# SparkFun_NEO-M8U.net
KiCad netlist of a schematic drawn in EAGLE
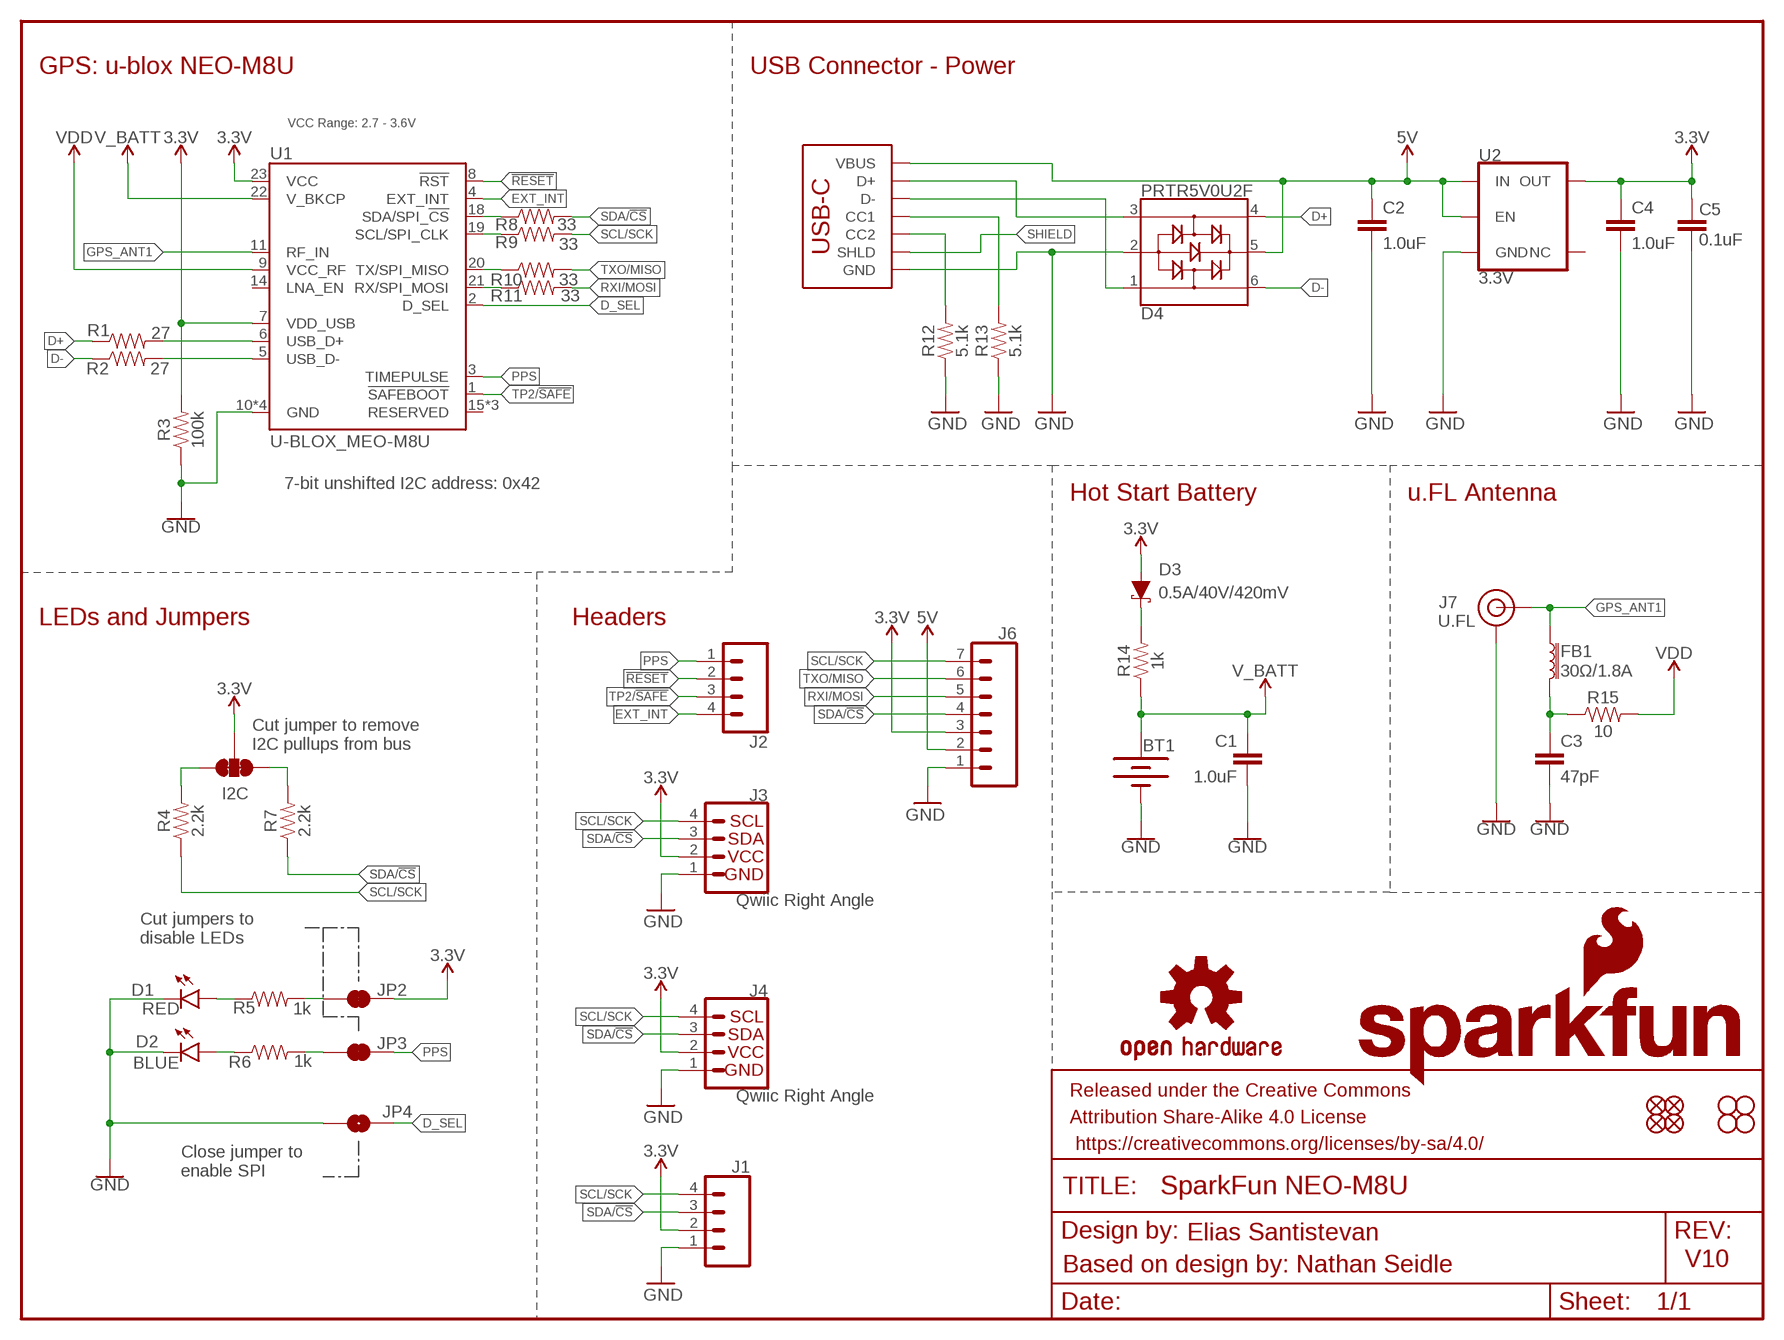
[diagram p0: schematic, sheet 1]

(export (version "E")
  (design (tool "Eeschema 10.0.6"))
  (components
    (comp (ref "BT1")
      (value "6.8MM_COIN_CELL")
      (footprint "eagle-import:ML414H_IV01E")
      (libsource (lib "eagle-import") (part "ML414H_IV01E_BATTERY"))
    )
    (comp (ref "C1")
      (value "1.0uF")
      (footprint "eagle-import:0603")
      (libsource (lib "eagle-import") (part "1.0UF-0603-16V-10%"))
    )
    (comp (ref "C2")
      (value "1.0uF")
      (footprint "eagle-import:0603")
      (libsource (lib "eagle-import") (part "1.0UF-0603-16V-10%"))
    )
    (comp (ref "C3")
      (value "47pF")
      (footprint "eagle-import:0603")
      (libsource (lib "eagle-import") (part "47PF-0603-50V-5%"))
    )
    (comp (ref "C4")
      (value "1.0uF")
      (footprint "eagle-import:0603")
      (libsource (lib "eagle-import") (part "1.0UF-0603-16V-10%"))
    )
    (comp (ref "C5")
      (value "0.1uF")
      (footprint "eagle-import:0603")
      (libsource (lib "eagle-import") (part "0.1UF-0603-25V-(+80/-20%)"))
    )
    (comp (ref "D1")
      (value "RED")
      (footprint "eagle-import:LED-0603")
      (libsource (lib "eagle-import") (part "LED-RED0603"))
    )
    (comp (ref "D2")
      (value "BLUE")
      (footprint "eagle-import:LED-0603")
      (libsource (lib "eagle-import") (part "LED-BLUE0603"))
    )
    (comp (ref "D3")
      (value "0.5A/40V/420mV")
      (footprint "eagle-import:SOD-323")
      (libsource (lib "eagle-import") (part "DIODE-SCHOTTKY-PMEG4005EJ"))
    )
    (comp (ref "D4")
      (value "PRTR5V0U2F")
      (footprint "eagle-import:SOT886")
      (libsource (lib "eagle-import") (part "PRTR5V0U2F"))
    )
    (comp (ref "FB1")
      (value "30Ω/1.8A")
      (footprint "eagle-import:0603")
      (libsource (lib "eagle-import") (part "FERRITE_BEAD-0603"))
    )
    (comp (ref "FRAME1")
      (value "FRAME-LETTER")
      (footprint "eagle-import:CREATIVE_COMMONS")
      (libsource (lib "eagle-import") (part "FRAME-LETTER"))
    )
    (comp (ref "J1")
      (value "CONN_041X04_NO_SILK")
      (footprint "eagle-import:1X04_NO_SILK")
      (libsource (lib "eagle-import") (part "CONN_041X04_NO_SILK"))
    )
    (comp (ref "J2")
      (value "CONN_041X04_NO_SILK")
      (footprint "eagle-import:1X04_NO_SILK")
      (libsource (lib "eagle-import") (part "CONN_041X04_NO_SILK"))
    )
    (comp (ref "J3")
      (value "Qwiic Right Angle")
      (footprint "eagle-import:JST04_1MM_RA")
      (libsource (lib "eagle-import") (part "I2C_STANDARDQWIIC"))
    )
    (comp (ref "J4")
      (value "Qwiic Right Angle")
      (footprint "eagle-import:JST04_1MM_RA")
      (libsource (lib "eagle-import") (part "I2C_STANDARDQWIIC"))
    )
    (comp (ref "J5")
      (value "USB_C_2-LAYER_PADS")
      (footprint "eagle-import:USB-C-16P-2LAYER-PADS")
      (libsource (lib "eagle-import") (part "USB_C_2-LAYER_PADS"))
    )
    (comp (ref "J6")
      (value "CONN_07NO_SILK")
      (footprint "eagle-import:1X07_NO_SILK")
      (libsource (lib "eagle-import") (part "CONN_07NO_SILK"))
    )
    (comp (ref "J7")
      (value "U.FL")
      (footprint "eagle-import:U.FL")
      (libsource (lib "eagle-import") (part "U.FL2PIN"))
    )
    (comp (ref "JP1")
      (value "JUMPER-SMT_3_2-NC_TRACE_SILK")
      (footprint "eagle-import:SMT-JUMPER_3_2-NC_TRACE_SILK")
      (libsource (lib "eagle-import") (part "JUMPER-SMT_3_2-NC_TRACE_SILK"))
    )
    (comp (ref "JP2")
      (value "JUMPER-SMT_2_NC_TRACE_SILK")
      (footprint "eagle-import:SMT-JUMPER_2_NC_TRACE_SILK")
      (libsource (lib "eagle-import") (part "JUMPER-SMT_2_NC_TRACE_SILK"))
    )
    (comp (ref "JP3")
      (value "JUMPER-SMT_2_NC_TRACE_SILK")
      (footprint "eagle-import:SMT-JUMPER_2_NC_TRACE_SILK")
      (libsource (lib "eagle-import") (part "JUMPER-SMT_2_NC_TRACE_SILK"))
    )
    (comp (ref "JP4")
      (value "JUMPER-SMT_2_NO_SILK")
      (footprint "eagle-import:SMT-JUMPER_2_NO_SILK")
      (libsource (lib "eagle-import") (part "JUMPER-SMT_2_NO_SILK"))
    )
    (comp (ref "JP5")
      (value "FIDUCIALUFIDUCIAL")
      (footprint "eagle-import:MICRO-FIDUCIAL")
      (libsource (lib "eagle-import") (part "FIDUCIALUFIDUCIAL"))
    )
    (comp (ref "JP6")
      (value "FIDUCIALUFIDUCIAL")
      (footprint "eagle-import:MICRO-FIDUCIAL")
      (libsource (lib "eagle-import") (part "FIDUCIALUFIDUCIAL"))
    )
    (comp (ref "JP7")
      (value "FIDUCIALUFIDUCIAL")
      (footprint "eagle-import:MICRO-FIDUCIAL")
      (libsource (lib "eagle-import") (part "FIDUCIALUFIDUCIAL"))
    )
    (comp (ref "JP8")
      (value "FIDUCIALUFIDUCIAL")
      (footprint "eagle-import:MICRO-FIDUCIAL")
      (libsource (lib "eagle-import") (part "FIDUCIALUFIDUCIAL"))
    )
    (comp (ref "JP9")
      (value "STAND-OFF")
      (footprint "eagle-import:STAND-OFF")
      (libsource (lib "eagle-import") (part "STAND-OFF"))
    )
    (comp (ref "JP10")
      (value "STAND-OFF")
      (footprint "eagle-import:STAND-OFF")
      (libsource (lib "eagle-import") (part "STAND-OFF"))
    )
    (comp (ref "JP11")
      (value "STAND-OFF")
      (footprint "eagle-import:STAND-OFF")
      (libsource (lib "eagle-import") (part "STAND-OFF"))
    )
    (comp (ref "JP12")
      (value "STAND-OFF")
      (footprint "eagle-import:STAND-OFF")
      (libsource (lib "eagle-import") (part "STAND-OFF"))
    )
    (comp (ref "LOGO1")
      (value "OSHW-LOGOMINI")
      (footprint "eagle-import:OSHW-LOGO-MINI")
      (libsource (lib "eagle-import") (part "OSHW-LOGOMINI"))
    )
    (comp (ref "LOGO2")
      (value "SFE_LOGO_NAME_FLAME.1_INCH")
      (footprint "eagle-import:SFE_LOGO_NAME_FLAME_.1")
      (libsource (lib "eagle-import") (part "SFE_LOGO_NAME_FLAME.1_INCH"))
    )
    (comp (ref "R1")
      (value "27")
      (footprint "eagle-import:0603")
      (libsource (lib "eagle-import") (part "27OHM-0603-1/10W-1%"))
    )
    (comp (ref "R2")
      (value "27")
      (footprint "eagle-import:0603")
      (libsource (lib "eagle-import") (part "27OHM-0603-1/10W-1%"))
    )
    (comp (ref "R3")
      (value "100k")
      (footprint "eagle-import:0603")
      (libsource (lib "eagle-import") (part "100KOHM-0603-1/10W-1%"))
    )
    (comp (ref "R4")
      (value "2.2k")
      (footprint "eagle-import:0603")
      (libsource (lib "eagle-import") (part "2.2KOHM-0603-1/10W-1%"))
    )
    (comp (ref "R5")
      (value "1k")
      (footprint "eagle-import:0603")
      (libsource (lib "eagle-import") (part "1KOHM-0603-1/10W-1%"))
    )
    (comp (ref "R6")
      (value "1k")
      (footprint "eagle-import:0603")
      (libsource (lib "eagle-import") (part "1KOHM-0603-1/10W-1%"))
    )
    (comp (ref "R7")
      (value "2.2k")
      (footprint "eagle-import:0603")
      (libsource (lib "eagle-import") (part "2.2KOHM-0603-1/10W-1%"))
    )
    (comp (ref "R8")
      (value "33")
      (footprint "eagle-import:0603")
      (libsource (lib "eagle-import") (part "33OHM-0603-1/10W-1%"))
    )
    (comp (ref "R9")
      (value "33")
      (footprint "eagle-import:0603")
      (libsource (lib "eagle-import") (part "33OHM-0603-1/10W-1%"))
    )
    (comp (ref "R10")
      (value "33")
      (footprint "eagle-import:0603")
      (libsource (lib "eagle-import") (part "33OHM-0603-1/10W-1%"))
    )
    (comp (ref "R11")
      (value "33")
      (footprint "eagle-import:0603")
      (libsource (lib "eagle-import") (part "33OHM-0603-1/10W-1%"))
    )
    (comp (ref "R12")
      (value "5.1k")
      (footprint "eagle-import:0603")
      (libsource (lib "eagle-import") (part "5.1KOHM5.1KOHM-0603-1/10W-1%"))
    )
    (comp (ref "R13")
      (value "5.1k")
      (footprint "eagle-import:0603")
      (libsource (lib "eagle-import") (part "5.1KOHM5.1KOHM-0603-1/10W-1%"))
    )
    (comp (ref "R14")
      (value "1k")
      (footprint "eagle-import:0603")
      (libsource (lib "eagle-import") (part "1KOHM-0603-1/10W-1%"))
    )
    (comp (ref "R15")
      (value "10")
      (footprint "eagle-import:0603")
      (libsource (lib "eagle-import") (part "10OHM-0603-1/10W-1%"))
    )
    (comp (ref "U1")
      (value "U-BLOX_MEO-M8U")
      (footprint "eagle-import:NEO-M9N_M8T_M8U")
      (libsource (lib "eagle-import") (part "U-BLOX_MEO-M8U"))
    )
    (comp (ref "U2")
      (value "3.3V")
      (footprint "eagle-import:SOT23-5")
      (libsource (lib "eagle-import") (part "V_REG_AP2112K-3.3V"))
    )
  )
  (nets
    (net (code "1") (name "/SDA{slash}~{CS}") (class "Default")
      (node (ref "J1") (pin "3") (pinfunction "3_3") (pintype "passive"))
      (node (ref "J3") (pin "3") (pinfunction "3_3") (pintype "passive"))
      (node (ref "J4") (pin "3") (pinfunction "3_3") (pintype "passive"))
      (node (ref "J6") (pin "4") (pinfunction "4_4") (pintype "passive"))
      (node (ref "R7") (pin "1") (pinfunction "1_1") (pintype "passive"))
      (node (ref "R8") (pin "2") (pinfunction "2_2") (pintype "passive"))
    )
    (net (code "2") (name "/TP2{slash}~{SAFE}") (class "Default")
      (node (ref "J2") (pin "3") (pinfunction "3_3") (pintype "passive"))
      (node (ref "U1") (pin "1") (pinfunction "~{SAFEBOOT}_1") (pintype "bidirectional"))
    )
    (net (code "3") (name "/~{RESET}") (class "Default")
      (node (ref "J2") (pin "2") (pinfunction "2_2") (pintype "passive"))
      (node (ref "U1") (pin "8") (pinfunction "~{RST}_8") (pintype "bidirectional"))
    )
    (net (code "4") (name "3.3V") (class "Default")
      (node (ref "C4") (pin "1") (pinfunction "1_1") (pintype "passive"))
      (node (ref "C5") (pin "2") (pinfunction "2_2") (pintype "passive"))
      (node (ref "D3") (pin "A") (pinfunction "A_A") (pintype "passive"))
      (node (ref "J1") (pin "2") (pinfunction "2_2") (pintype "passive"))
      (node (ref "J3") (pin "2") (pinfunction "2_2") (pintype "power_in"))
      (node (ref "J4") (pin "2") (pinfunction "2_2") (pintype "power_in"))
      (node (ref "J6") (pin "3") (pinfunction "3_3") (pintype "passive"))
      (node (ref "JP1") (pin "2") (pinfunction "2_2") (pintype "passive"))
      (node (ref "JP2") (pin "2") (pinfunction "2_2") (pintype "passive"))
      (node (ref "R3") (pin "2") (pinfunction "2_2") (pintype "passive"))
      (node (ref "U1") (pin "23") (pinfunction "VCC_23") (pintype "bidirectional"))
      (node (ref "U1") (pin "7") (pinfunction "VDD_USB_7") (pintype "bidirectional"))
      (node (ref "U2") (pin "5") (pinfunction "OUT_5") (pintype "passive"))
    )
    (net (code "5") (name "5V") (class "Default")
      (node (ref "C2") (pin "1") (pinfunction "1_1") (pintype "passive"))
      (node (ref "D4") (pin "5") (pinfunction "5_5") (pintype "bidirectional"))
      (node (ref "J5") (pin "VBUS1") (pinfunction "VBUS_VBUS1") (pintype "bidirectional"))
      (node (ref "J5") (pin "VBUS2") (pinfunction "VBUS_VBUS2") (pintype "bidirectional"))
      (node (ref "J6") (pin "2") (pinfunction "2_2") (pintype "passive"))
      (node (ref "U2") (pin "1") (pinfunction "IN_1") (pintype "input"))
      (node (ref "U2") (pin "3") (pinfunction "EN_3") (pintype "input"))
    )
    (net (code "6") (name "D+") (class "Default")
      (node (ref "D4") (pin "4") (pinfunction "4_4") (pintype "bidirectional"))
      (node (ref "R1") (pin "1") (pinfunction "1_1") (pintype "passive"))
    )
    (net (code "7") (name "D-") (class "Default")
      (node (ref "D4") (pin "6") (pinfunction "6_6") (pintype "bidirectional"))
      (node (ref "R2") (pin "1") (pinfunction "1_1") (pintype "passive"))
    )
    (net (code "8") (name "D_SEL") (class "Default")
      (node (ref "JP4") (pin "2") (pinfunction "2_2") (pintype "passive"))
      (node (ref "U1") (pin "2") (pinfunction "D_SEL_2") (pintype "bidirectional"))
    )
    (net (code "9") (name "EXT_INT") (class "Default")
      (node (ref "J2") (pin "4") (pinfunction "4_4") (pintype "passive"))
      (node (ref "U1") (pin "4") (pinfunction "EXT_INT_4") (pintype "bidirectional"))
    )
    (net (code "10") (name "GND") (class "Default")
      (node (ref "BT1") (pin "-") (pinfunction "-_-") (pintype "power_in"))
      (node (ref "C1") (pin "2") (pinfunction "2_2") (pintype "passive"))
      (node (ref "C2") (pin "2") (pinfunction "2_2") (pintype "passive"))
      (node (ref "C3") (pin "2") (pinfunction "2_2") (pintype "passive"))
      (node (ref "C4") (pin "2") (pinfunction "2_2") (pintype "passive"))
      (node (ref "C5") (pin "1") (pinfunction "1_1") (pintype "passive"))
      (node (ref "D1") (pin "C") (pinfunction "C_C") (pintype "passive"))
      (node (ref "D2") (pin "C") (pinfunction "C_C") (pintype "passive"))
      (node (ref "D4") (pin "2") (pinfunction "2_2") (pintype "bidirectional"))
      (node (ref "J1") (pin "1") (pinfunction "1_1") (pintype "passive"))
      (node (ref "J3") (pin "1") (pinfunction "1_1") (pintype "power_in"))
      (node (ref "J4") (pin "1") (pinfunction "1_1") (pintype "power_in"))
      (node (ref "J5") (pin "GND") (pinfunction "GND_GND") (pintype "bidirectional"))
      (node (ref "J5") (pin "GND2") (pinfunction "GND_GND2") (pintype "bidirectional"))
      (node (ref "J6") (pin "1") (pinfunction "1_1") (pintype "passive"))
      (node (ref "J7") (pin "1") (pinfunction "GND_1") (pintype "bidirectional"))
      (node (ref "J7") (pin "2") (pinfunction "GND_2") (pintype "bidirectional"))
      (node (ref "JP4") (pin "1") (pinfunction "1_1") (pintype "passive"))
      (node (ref "R12") (pin "1") (pinfunction "1_1") (pintype "passive"))
      (node (ref "R13") (pin "1") (pinfunction "1_1") (pintype "passive"))
      (node (ref "R3") (pin "1") (pinfunction "1_1") (pintype "passive"))
      (node (ref "U1") (pin "10") (pinfunction "GND_10") (pintype "bidirectional"))
      (node (ref "U1") (pin "12") (pinfunction "GND_12") (pintype "bidirectional"))
      (node (ref "U1") (pin "13") (pinfunction "GND_13") (pintype "bidirectional"))
      (node (ref "U1") (pin "24") (pinfunction "GND_24") (pintype "bidirectional"))
      (node (ref "U2") (pin "2") (pinfunction "GND_2") (pintype "input"))
    )
    (net (code "11") (name "GPS_ANT1") (class "Default")
      (node (ref "FB1") (pin "1") (pinfunction "1_1") (pintype "passive"))
      (node (ref "J7") (pin "FEED") (pinfunction "SIGNAL_FEED") (pintype "bidirectional"))
      (node (ref "U1") (pin "11") (pinfunction "RF_IN_11") (pintype "bidirectional"))
    )
    (net (code "12") (name "Net-(C3-Pad1)") (class "Default")
      (node (ref "C3") (pin "1") (pinfunction "1_1") (pintype "passive"))
      (node (ref "FB1") (pin "2") (pinfunction "2_2") (pintype "passive"))
      (node (ref "R15") (pin "1") (pinfunction "1_1") (pintype "passive"))
    )
    (net (code "13") (name "Net-(D1-PadA)") (class "Default")
      (node (ref "D1") (pin "A") (pinfunction "A_A") (pintype "passive"))
      (node (ref "R5") (pin "1") (pinfunction "1_1") (pintype "passive"))
    )
    (net (code "14") (name "Net-(D2-PadA)") (class "Default")
      (node (ref "D2") (pin "A") (pinfunction "A_A") (pintype "passive"))
      (node (ref "R6") (pin "1") (pinfunction "1_1") (pintype "passive"))
    )
    (net (code "15") (name "Net-(D3-PadC)") (class "Default")
      (node (ref "D3") (pin "C") (pinfunction "C_C") (pintype "passive"))
      (node (ref "R14") (pin "2") (pinfunction "2_2") (pintype "passive"))
    )
    (net (code "16") (name "Net-(D4-Pad1)") (class "Default")
      (node (ref "D4") (pin "1") (pinfunction "1_1") (pintype "bidirectional"))
      (node (ref "J5") (pin "A7") (pinfunction "D-_A7") (pintype "bidirectional"))
      (node (ref "J5") (pin "B7") (pinfunction "D-_B7") (pintype "bidirectional"))
    )
    (net (code "17") (name "Net-(D4-Pad3)") (class "Default")
      (node (ref "D4") (pin "3") (pinfunction "3_3") (pintype "bidirectional"))
      (node (ref "J5") (pin "A6") (pinfunction "D+_A6") (pintype "bidirectional"))
      (node (ref "J5") (pin "B6") (pinfunction "D+_B6") (pintype "bidirectional"))
    )
    (net (code "18") (name "Net-(J5-CC1)") (class "Default")
      (node (ref "J5") (pin "A5") (pinfunction "CC1_A5") (pintype "bidirectional"))
      (node (ref "R13") (pin "2") (pinfunction "2_2") (pintype "passive"))
    )
    (net (code "19") (name "Net-(J5-CC2)") (class "Default")
      (node (ref "J5") (pin "B5") (pinfunction "CC2_B5") (pintype "bidirectional"))
      (node (ref "R12") (pin "2") (pinfunction "2_2") (pintype "passive"))
    )
    (net (code "20") (name "Net-(JP1-Pad1)") (class "Default")
      (node (ref "JP1") (pin "1") (pinfunction "1_1") (pintype "passive"))
      (node (ref "R7") (pin "2") (pinfunction "2_2") (pintype "passive"))
    )
    (net (code "21") (name "Net-(JP1-Pad3)") (class "Default")
      (node (ref "JP1") (pin "3") (pinfunction "3_3") (pintype "passive"))
      (node (ref "R4") (pin "2") (pinfunction "2_2") (pintype "passive"))
    )
    (net (code "22") (name "Net-(JP2-Pad1)") (class "Default")
      (node (ref "JP2") (pin "1") (pinfunction "1_1") (pintype "passive"))
      (node (ref "R5") (pin "2") (pinfunction "2_2") (pintype "passive"))
    )
    (net (code "23") (name "Net-(JP3-Pad1)") (class "Default")
      (node (ref "JP3") (pin "1") (pinfunction "1_1") (pintype "passive"))
      (node (ref "R6") (pin "2") (pinfunction "2_2") (pintype "passive"))
    )
    (net (code "24") (name "Net-(U1-RX{slash}SPI_MOSI)") (class "Default")
      (node (ref "R11") (pin "1") (pinfunction "1_1") (pintype "passive"))
      (node (ref "U1") (pin "21") (pinfunction "RX/SPI_MOSI_21") (pintype "bidirectional"))
    )
    (net (code "25") (name "Net-(U1-SCL{slash}SPI_CLK)") (class "Default")
      (node (ref "R9") (pin "1") (pinfunction "1_1") (pintype "passive"))
      (node (ref "U1") (pin "19") (pinfunction "SCL/SPI_CLK_19") (pintype "bidirectional"))
    )
    (net (code "26") (name "Net-(U1-SDA{slash}SPI_~{CS})") (class "Default")
      (node (ref "R8") (pin "1") (pinfunction "1_1") (pintype "passive"))
      (node (ref "U1") (pin "18") (pinfunction "SDA/SPI_~{CS}_18") (pintype "bidirectional"))
    )
    (net (code "27") (name "Net-(U1-TX{slash}SPI_MISO)") (class "Default")
      (node (ref "R10") (pin "1") (pinfunction "1_1") (pintype "passive"))
      (node (ref "U1") (pin "20") (pinfunction "TX/SPI_MISO_20") (pintype "bidirectional"))
    )
    (net (code "28") (name "Net-(U1-USB_D+)") (class "Default")
      (node (ref "R1") (pin "2") (pinfunction "2_2") (pintype "passive"))
      (node (ref "U1") (pin "6") (pinfunction "USB_D+_6") (pintype "bidirectional"))
    )
    (net (code "29") (name "Net-(U1-USB_D-)") (class "Default")
      (node (ref "R2") (pin "2") (pinfunction "2_2") (pintype "passive"))
      (node (ref "U1") (pin "5") (pinfunction "USB_D-_5") (pintype "bidirectional"))
    )
    (net (code "30") (name "PPS") (class "Default")
      (node (ref "J2") (pin "1") (pinfunction "1_1") (pintype "passive"))
      (node (ref "JP3") (pin "2") (pinfunction "2_2") (pintype "passive"))
      (node (ref "U1") (pin "3") (pinfunction "TIMEPULSE_3") (pintype "bidirectional"))
    )
    (net (code "31") (name "RXI{slash}MOSI") (class "Default")
      (node (ref "J6") (pin "5") (pinfunction "5_5") (pintype "passive"))
      (node (ref "R11") (pin "2") (pinfunction "2_2") (pintype "passive"))
    )
    (net (code "32") (name "SCL{slash}SCK") (class "Default")
      (node (ref "J1") (pin "4") (pinfunction "4_4") (pintype "passive"))
      (node (ref "J3") (pin "4") (pinfunction "4_4") (pintype "passive"))
      (node (ref "J4") (pin "4") (pinfunction "4_4") (pintype "passive"))
      (node (ref "J6") (pin "7") (pinfunction "7_7") (pintype "passive"))
      (node (ref "R4") (pin "1") (pinfunction "1_1") (pintype "passive"))
      (node (ref "R9") (pin "2") (pinfunction "2_2") (pintype "passive"))
    )
    (net (code "33") (name "SHIELD") (class "Default")
      (node (ref "J5") (pin "SHLD1") (pinfunction "SHLD_SHLD1") (pintype "bidirectional"))
      (node (ref "J5") (pin "SHLD2") (pinfunction "SHLD_SHLD2") (pintype "bidirectional"))
      (node (ref "J5") (pin "SHLD3") (pinfunction "SHLD_SHLD3") (pintype "bidirectional"))
      (node (ref "J5") (pin "SHLD4") (pinfunction "SHLD_SHLD4") (pintype "bidirectional"))
    )
    (net (code "34") (name "TXO{slash}MISO") (class "Default")
      (node (ref "J6") (pin "6") (pinfunction "6_6") (pintype "passive"))
      (node (ref "R10") (pin "2") (pinfunction "2_2") (pintype "passive"))
    )
    (net (code "35") (name "VDD") (class "Default")
      (node (ref "R15") (pin "2") (pinfunction "2_2") (pintype "passive"))
      (node (ref "U1") (pin "9") (pinfunction "VCC_RF_9") (pintype "bidirectional"))
    )
    (net (code "36") (name "V_BATT") (class "Default")
      (node (ref "BT1") (pin "+") (pinfunction "+_+") (pintype "power_in"))
      (node (ref "C1") (pin "1") (pinfunction "1_1") (pintype "passive"))
      (node (ref "R14") (pin "1") (pinfunction "1_1") (pintype "passive"))
      (node (ref "U1") (pin "22") (pinfunction "V_BKCP_22") (pintype "bidirectional"))
    )
    (net (code "37") (name "unconnected-(U1-LNA_EN-Pad14)") (class "Default")
      (node (ref "U1") (pin "14") (pinfunction "LNA_EN_14") (pintype "bidirectional"))
    )
    (net (code "38") (name "unconnected-(U1-RESERVED-Pad15)") (class "Default")
      (node (ref "U1") (pin "15") (pinfunction "RESERVED_15") (pintype "no_connect"))
    )
    (net (code "39") (name "unconnected-(U1-RESERVED-Pad16)") (class "Default")
      (node (ref "U1") (pin "16") (pinfunction "RESERVED_16") (pintype "no_connect"))
    )
    (net (code "40") (name "unconnected-(U1-RESERVED-Pad17)") (class "Default")
      (node (ref "U1") (pin "17") (pinfunction "RESERVED_17") (pintype "no_connect"))
    )
    (net (code "41") (name "unconnected-(U2-NC-Pad4)") (class "Default")
      (node (ref "U2") (pin "4") (pinfunction "NC_4") (pintype "no_connect"))
    )
  )
)
